# LnMasterInterface.net
KiCad netlist of a schematic drawn in EAGLE
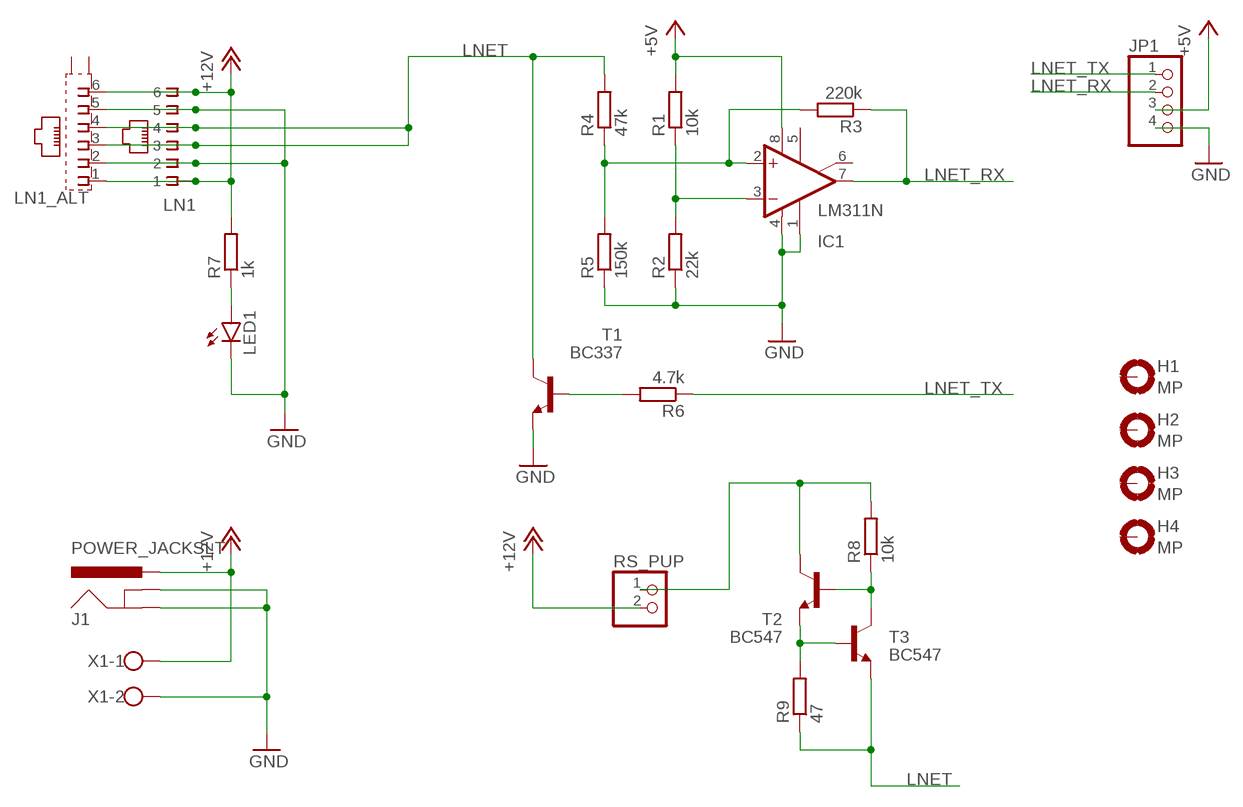
[diagram p0: schematic, sheet 1]

(export (version "E")
  (design (tool "Eeschema 10.0.6"))
  (components
    (comp (ref "H1")
      (value "MP")
      (footprint "eagle-import:3,0-PAD")
      (libsource (lib "eagle-import") (part "MOUNT-PAD-ROUND3.0"))
    )
    (comp (ref "H2")
      (value "MP")
      (footprint "eagle-import:3,0-PAD")
      (libsource (lib "eagle-import") (part "MOUNT-PAD-ROUND3.0"))
    )
    (comp (ref "H3")
      (value "MP")
      (footprint "eagle-import:3,0-PAD")
      (libsource (lib "eagle-import") (part "MOUNT-PAD-ROUND3.0"))
    )
    (comp (ref "H4")
      (value "MP")
      (footprint "eagle-import:3,0-PAD")
      (libsource (lib "eagle-import") (part "MOUNT-PAD-ROUND3.0"))
    )
    (comp (ref "IC1")
      (value "LM311N")
      (footprint "eagle-import:DIL08")
      (libsource (lib "eagle-import") (part "LM311N"))
    )
    (comp (ref "J1")
      (value "POWER_JACKSLT")
      (footprint "eagle-import:POWER_JACK_SLOT")
      (libsource (lib "eagle-import") (part "POWER_JACKSLT"))
    )
    (comp (ref "JP1")
      (value "PINHD-1X4")
      (footprint "eagle-import:1X04")
      (libsource (lib "eagle-import") (part "PINHD-1X4"))
    )
    (comp (ref "LED1")
      (value "LED3MM")
      (footprint "eagle-import:LED3MM")
      (libsource (lib "eagle-import") (part "LED3MM"))
    )
    (comp (ref "LN1")
      (value "RJ11-6X")
      (footprint "eagle-import:RJ11-NO_SHIELD")
      (libsource (lib "eagle-import") (part "RJ11-6X"))
    )
    (comp (ref "LN1_ALT")
      (value "YH-55-10")
      (footprint "eagle-import:YH-55-10")
      (libsource (lib "eagle-import") (part "YH-55-10"))
    )
    (comp (ref "R1")
      (value "10k")
      (footprint "eagle-import:0207_2V")
      (libsource (lib "eagle-import") (part "R-EU_0207/2V"))
    )
    (comp (ref "R2")
      (value "22k")
      (footprint "eagle-import:0207_2V")
      (libsource (lib "eagle-import") (part "R-EU_0207/2V"))
    )
    (comp (ref "R3")
      (value "220k")
      (footprint "eagle-import:0207_2V")
      (libsource (lib "eagle-import") (part "R-EU_0207/2V"))
    )
    (comp (ref "R4")
      (value "47k")
      (footprint "eagle-import:0207_2V")
      (libsource (lib "eagle-import") (part "R-EU_0207/2V"))
    )
    (comp (ref "R5")
      (value "150k")
      (footprint "eagle-import:0207_2V")
      (libsource (lib "eagle-import") (part "R-EU_0207/2V"))
    )
    (comp (ref "R6")
      (value "4.7k")
      (footprint "eagle-import:0207_2V")
      (libsource (lib "eagle-import") (part "R-EU_0207/2V"))
    )
    (comp (ref "R7")
      (value "1k")
      (footprint "eagle-import:0207_2V")
      (libsource (lib "eagle-import") (part "R-EU_0207/2V"))
    )
    (comp (ref "R8")
      (value "10k")
      (footprint "eagle-import:0207_2V")
      (libsource (lib "eagle-import") (part "R-EU_0207/2V"))
    )
    (comp (ref "R9")
      (value "47")
      (footprint "eagle-import:0207_2V")
      (libsource (lib "eagle-import") (part "R-EU_0207/2V"))
    )
    (comp (ref "RS_PUP")
      (value "PINHD-1X2")
      (footprint "eagle-import:1X02")
      (libsource (lib "eagle-import") (part "PINHD-1X2"))
    )
    (comp (ref "T1")
      (value "BC337")
      (footprint "eagle-import:TO92")
      (libsource (lib "eagle-import") (part "BC337"))
    )
    (comp (ref "T2")
      (value "BC547")
      (footprint "eagle-import:TO92")
      (libsource (lib "eagle-import") (part "BC547"))
    )
    (comp (ref "T3")
      (value "BC547")
      (footprint "eagle-import:TO92")
      (libsource (lib "eagle-import") (part "BC547"))
    )
    (comp (ref "X1")
      (value "W237-102")
      (footprint "eagle-import:W237-102")
      (fields (field (name "MPN") "237-102"))
      (libsource (lib "eagle-import") (part "W237-102"))
    )
  )
  (nets
    (net (code "1") (name "+5V") (class "Default")
      (node (ref "IC1") (pin "8") (pinfunction "V+_8") (pintype "power_in"))
      (node (ref "JP1") (pin "3") (pinfunction "3_3") (pintype "passive"))
      (node (ref "R1") (pin "2") (pinfunction "2_2") (pintype "passive"))
    )
    (net (code "2") (name "+12V") (class "Default")
      (node (ref "J1") (pin "PWR") (pinfunction "PWR_PWR") (pintype "bidirectional"))
      (node (ref "LN1") (pin "1") (pinfunction "1_1") (pintype "passive"))
      (node (ref "LN1") (pin "6") (pinfunction "6_6") (pintype "passive"))
      (node (ref "LN1_ALT") (pin "1") (pinfunction "1_1") (pintype "passive"))
      (node (ref "LN1_ALT") (pin "6") (pinfunction "6_6") (pintype "passive"))
      (node (ref "R7") (pin "2") (pinfunction "2_2") (pintype "passive"))
      (node (ref "RS_PUP") (pin "2") (pinfunction "2_2") (pintype "passive"))
      (node (ref "X1") (pin "1") (pinfunction "KL_1") (pintype "passive"))
    )
    (net (code "3") (name "/LNET") (class "Default")
      (node (ref "LN1") (pin "3") (pinfunction "3_3") (pintype "passive"))
      (node (ref "LN1") (pin "4") (pinfunction "4_4") (pintype "passive"))
      (node (ref "LN1_ALT") (pin "3") (pinfunction "3_3") (pintype "passive"))
      (node (ref "LN1_ALT") (pin "4") (pinfunction "4_4") (pintype "passive"))
      (node (ref "R4") (pin "2") (pinfunction "2_2") (pintype "passive"))
      (node (ref "R9") (pin "1") (pinfunction "1_1") (pintype "passive"))
      (node (ref "T1") (pin "3") (pinfunction "C_3") (pintype "passive"))
      (node (ref "T3") (pin "1") (pinfunction "E_1") (pintype "passive"))
    )
    (net (code "4") (name "/LNET_RX") (class "Default")
      (node (ref "IC1") (pin "7") (pinfunction "OUT_7") (pintype "output"))
      (node (ref "JP1") (pin "2") (pinfunction "2_2") (pintype "passive"))
      (node (ref "R3") (pin "1") (pinfunction "1_1") (pintype "passive"))
    )
    (net (code "5") (name "/LNET_TX") (class "Default")
      (node (ref "JP1") (pin "1") (pinfunction "1_1") (pintype "passive"))
      (node (ref "R6") (pin "1") (pinfunction "1_1") (pintype "passive"))
    )
    (net (code "6") (name "GND") (class "Default")
      (node (ref "IC1") (pin "1") (pinfunction "GND_1") (pintype "passive"))
      (node (ref "IC1") (pin "4") (pinfunction "V-_4") (pintype "power_in"))
      (node (ref "J1") (pin "GND@1") (pinfunction "GNDBREAK_GND@1") (pintype "bidirectional"))
      (node (ref "J1") (pin "GND@2") (pinfunction "GND_GND@2") (pintype "bidirectional"))
      (node (ref "JP1") (pin "4") (pinfunction "4_4") (pintype "passive"))
      (node (ref "LED1") (pin "K") (pinfunction "C_K") (pintype "passive"))
      (node (ref "LN1") (pin "2") (pinfunction "2_2") (pintype "passive"))
      (node (ref "LN1") (pin "5") (pinfunction "5_5") (pintype "passive"))
      (node (ref "LN1_ALT") (pin "2") (pinfunction "2_2") (pintype "passive"))
      (node (ref "LN1_ALT") (pin "5") (pinfunction "5_5") (pintype "passive"))
      (node (ref "R2") (pin "1") (pinfunction "1_1") (pintype "passive"))
      (node (ref "R5") (pin "1") (pinfunction "1_1") (pintype "passive"))
      (node (ref "T1") (pin "1") (pinfunction "E_1") (pintype "passive"))
      (node (ref "X1") (pin "2") (pinfunction "KL_2") (pintype "passive"))
    )
    (net (code "7") (name "Net-(IC1-+IN)") (class "Default")
      (node (ref "IC1") (pin "2") (pinfunction "+IN_2") (pintype "input"))
      (node (ref "R3") (pin "2") (pinfunction "2_2") (pintype "passive"))
      (node (ref "R4") (pin "1") (pinfunction "1_1") (pintype "passive"))
      (node (ref "R5") (pin "2") (pinfunction "2_2") (pintype "passive"))
    )
    (net (code "8") (name "Net-(IC1--IN)") (class "Default")
      (node (ref "IC1") (pin "3") (pinfunction "-IN_3") (pintype "input"))
      (node (ref "R1") (pin "1") (pinfunction "1_1") (pintype "passive"))
      (node (ref "R2") (pin "2") (pinfunction "2_2") (pintype "passive"))
    )
    (net (code "9") (name "Net-(LED1-PadA)") (class "Default")
      (node (ref "LED1") (pin "A") (pinfunction "A_A") (pintype "passive"))
      (node (ref "R7") (pin "1") (pinfunction "1_1") (pintype "passive"))
    )
    (net (code "10") (name "Net-(T1-B)") (class "Default")
      (node (ref "R6") (pin "2") (pinfunction "2_2") (pintype "passive"))
      (node (ref "T1") (pin "2") (pinfunction "B_2") (pintype "passive"))
    )
    (net (code "11") (name "Net-(T2-B)") (class "Default")
      (node (ref "R8") (pin "1") (pinfunction "1_1") (pintype "passive"))
      (node (ref "T2") (pin "2") (pinfunction "B_2") (pintype "passive"))
      (node (ref "T3") (pin "3") (pinfunction "C_3") (pintype "passive"))
    )
    (net (code "12") (name "Net-(T2-C)") (class "Default")
      (node (ref "R8") (pin "2") (pinfunction "2_2") (pintype "passive"))
      (node (ref "RS_PUP") (pin "1") (pinfunction "1_1") (pintype "passive"))
      (node (ref "T2") (pin "3") (pinfunction "C_3") (pintype "passive"))
    )
    (net (code "13") (name "Net-(T2-E)") (class "Default")
      (node (ref "R9") (pin "2") (pinfunction "2_2") (pintype "passive"))
      (node (ref "T2") (pin "1") (pinfunction "E_1") (pintype "passive"))
      (node (ref "T3") (pin "2") (pinfunction "B_2") (pintype "passive"))
    )
    (net (code "14") (name "unconnected-(H1-MOUNT-PadB3,0)") (class "Default")
      (node (ref "H1") (pin "B3,0") (pinfunction "MOUNT_B3,0") (pintype "passive"))
    )
    (net (code "15") (name "unconnected-(H2-MOUNT-PadB3,0)") (class "Default")
      (node (ref "H2") (pin "B3,0") (pinfunction "MOUNT_B3,0") (pintype "passive"))
    )
    (net (code "16") (name "unconnected-(H3-MOUNT-PadB3,0)") (class "Default")
      (node (ref "H3") (pin "B3,0") (pinfunction "MOUNT_B3,0") (pintype "passive"))
    )
    (net (code "17") (name "unconnected-(H4-MOUNT-PadB3,0)") (class "Default")
      (node (ref "H4") (pin "B3,0") (pinfunction "MOUNT_B3,0") (pintype "passive"))
    )
    (net (code "18") (name "unconnected-(IC1-ON-Pad5)") (class "Default")
      (node (ref "IC1") (pin "5") (pinfunction "ON_5") (pintype "passive"))
    )
    (net (code "19") (name "unconnected-(IC1-ON{slash}STR-Pad6)") (class "Default")
      (node (ref "IC1") (pin "6") (pinfunction "ON/STR_6") (pintype "passive"))
    )
    (net (code "20") (name "unconnected-(LN1_ALT-S-PadS1)") (class "Default")
      (node (ref "LN1_ALT") (pin "S1") (pinfunction "S_S1") (pintype "passive"))
    )
    (net (code "21") (name "unconnected-(LN1_ALT-S-PadS2)") (class "Default")
      (node (ref "LN1_ALT") (pin "S2") (pinfunction "S_S2") (pintype "passive"))
    )
  )
)
